# misc_A.net
KiCad netlist of a schematic drawn in Altium Designer
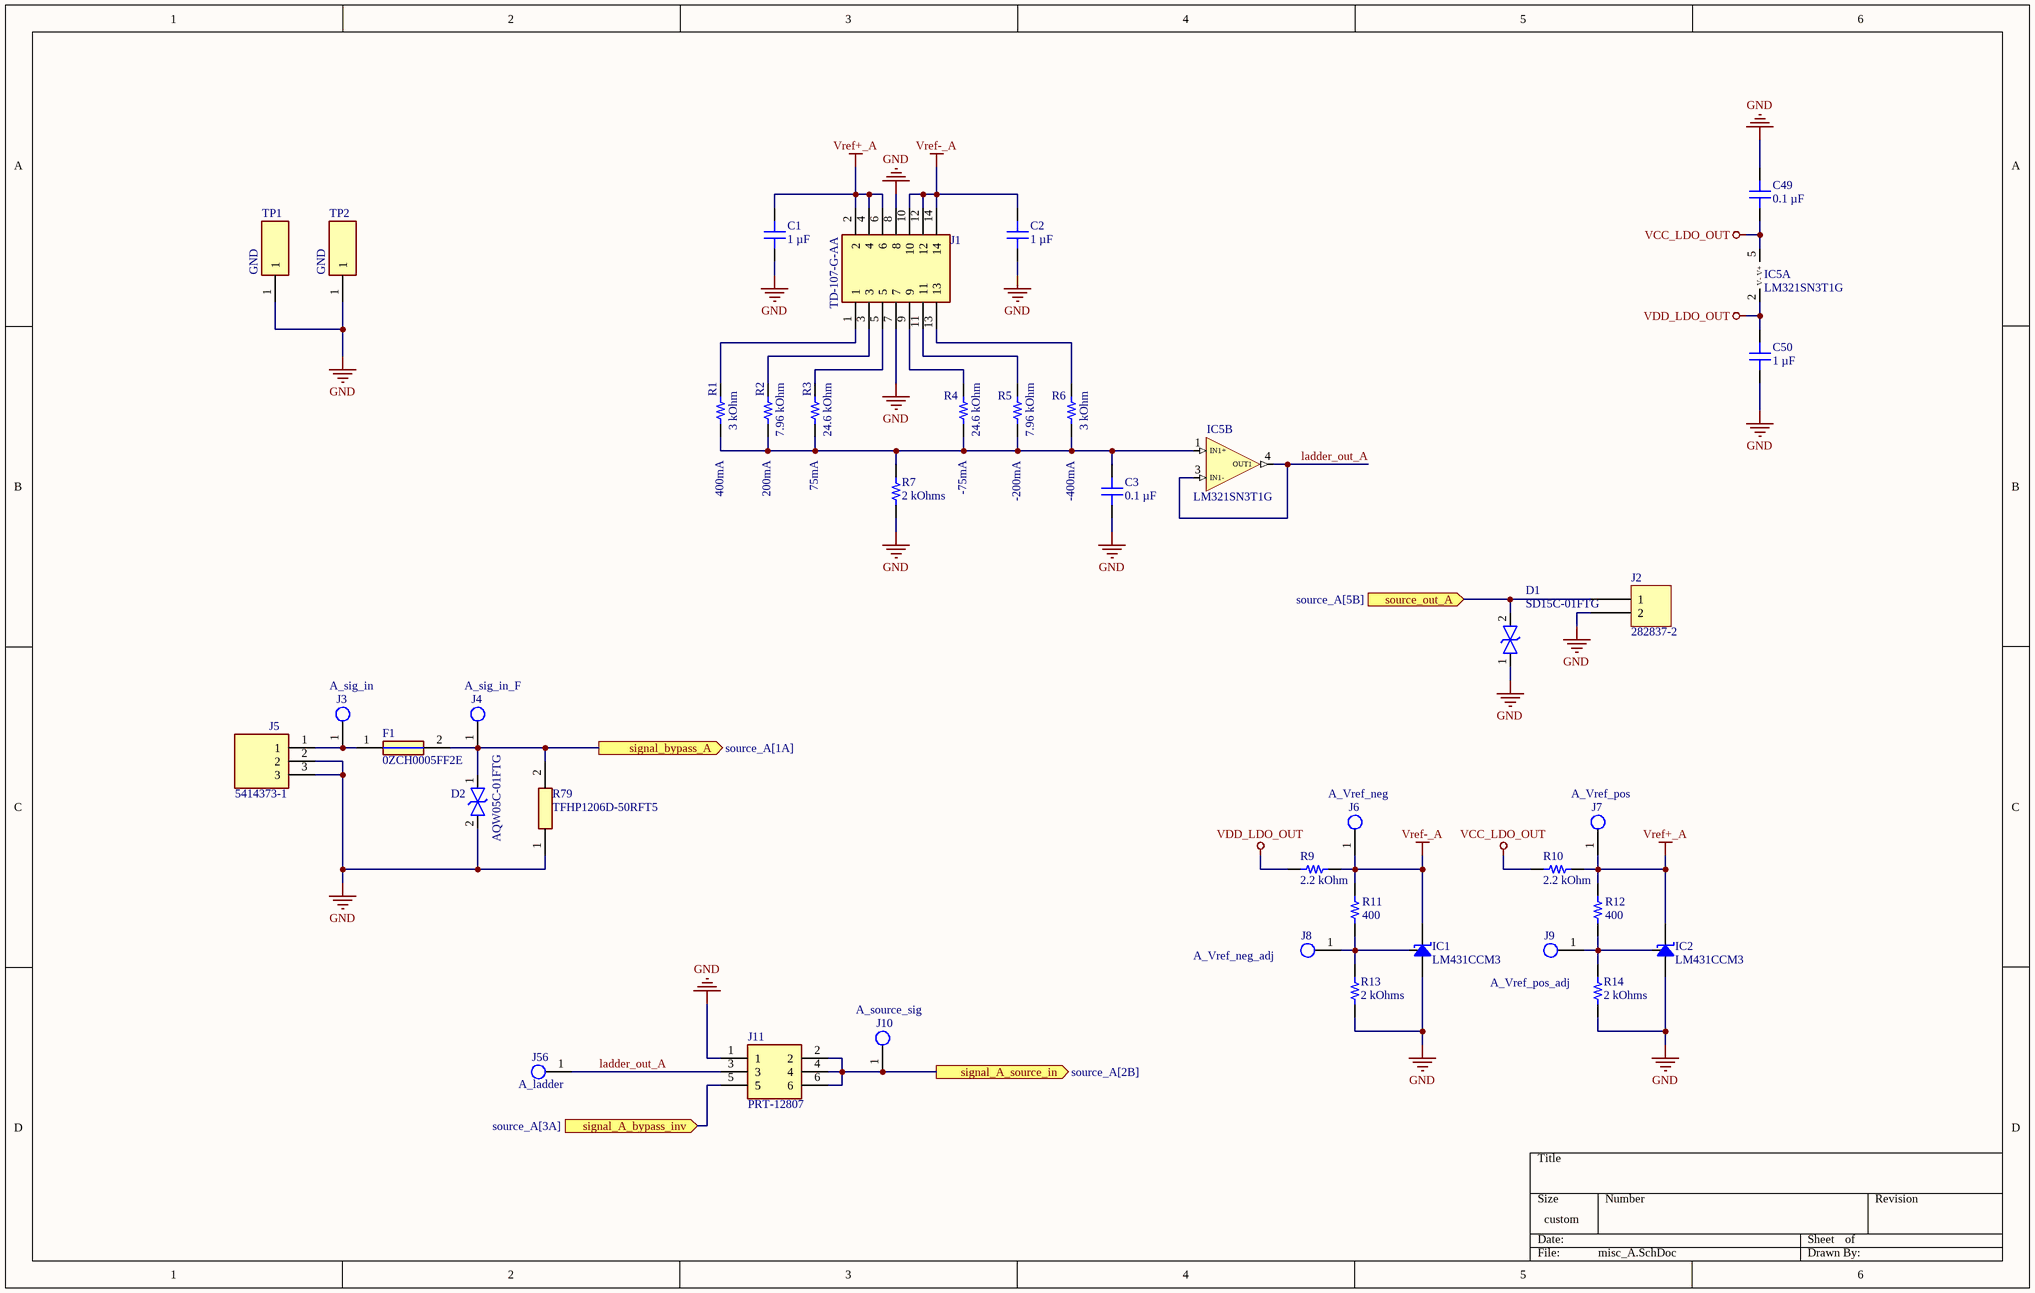
[diagram p0: misc_A.SchDoc]

(export (version "E")
  (design (tool "Eeschema 10.0.6"))
  (components
    (comp (ref "C1")
      (value "1 µF")
      (footprint "CAP 1206_3216 - 0.8MM")
      (description "CAP CER 1UF 50V X7R 1206")
      (fields
        (field (name "PART NUMBER") "885012208093")
        (field (name "CAPACITANCE") "1 µF")
        (field (name "MANUFACTURER") "Würth Elektronik")
      )
      (libsource (lib "Celestial Altium Library - altium_library") (part "Capacitor"))
    )
    (comp (ref "C2")
      (value "1 µF")
      (footprint "CAP 1206_3216 - 0.8MM")
      (description "CAP CER 1UF 50V X7R 1206")
      (fields
        (field (name "PART NUMBER") "885012208093")
        (field (name "CAPACITANCE") "1 µF")
        (field (name "MANUFACTURER") "Würth Elektronik")
      )
      (libsource (lib "Celestial Altium Library - altium_library") (part "Capacitor"))
    )
    (comp (ref "C3")
      (value "0.1 µF")
      (footprint "CAP 1206_3216 - 0.8MM")
      (description "CAP CER 0.1UF 50V X7R 1206")
      (fields
        (field (name "PART NUMBER") "885012208087")
        (field (name "CAPACITANCE") "0.1 µF")
        (field (name "MANUFACTURER") "Würth Elektronik")
      )
      (libsource (lib "Celestial Altium Library - altium_library") (part "Capacitor"))
    )
    (comp (ref "C49")
      (value "0.1 µF")
      (footprint "CAP 1206_3216 - 0.8MM")
      (description "CAP CER 0.1UF 50V X7R 1206")
      (fields
        (field (name "PART NUMBER") "885012208087")
        (field (name "CAPACITANCE") "0.1 µF")
        (field (name "MANUFACTURER") "Würth Elektronik")
      )
      (libsource (lib "Celestial Altium Library - altium_library") (part "Capacitor"))
    )
    (comp (ref "C50")
      (value "1 µF")
      (footprint "CAP 1206_3216 - 0.8MM")
      (description "CAP CER 1UF 50V X7R 1206")
      (fields
        (field (name "PART NUMBER") "885012208093")
        (field (name "CAPACITANCE") "1 µF")
        (field (name "MANUFACTURER") "Würth Elektronik")
      )
      (libsource (lib "Celestial Altium Library - altium_library") (part "Capacitor"))
    )
    (comp (ref "D1")
      (value "SD15C-01FTG")
      (footprint "za_koncar:SD15C01FTG")
      (description "TVS Diode (Bi-directional)")
      (fields (field (name "MOUSER PART NUMBER") "576-SD15C-01FTG"))
      (libsource (lib "za_koncar") (part "SD15C-01FTG"))
    )
    (comp (ref "D2")
      (value "AQW05C-01FTG")
      (footprint "SOD2613X100N")
      (description "TVS Diode (Bi-directional)")
      (fields (field (name "MOUSER PART NUMBER") "576-AQW05C-01FTG"))
      (libsource (lib "za_koncar") (part "AQW05C-01FTG"))
    )
    (comp (ref "F1")
      (value "0ZCH0005FF2E")
      (footprint "FUSC3226X115N")
      (description "Fuse")
      (fields (field (name "MOUSER PART NUMBER") "530-0ZCH0005FF2E"))
      (libsource (lib "za_koncar") (part "0ZCH0005FF2E"))
    )
    (comp (ref "IC1")
      (value "LM431CCM3")
      (footprint "SOT96P240X110-3N")
      (description "Integrated Circuit")
      (fields
        (field (name "MANUFACTURER_PART_NUMBER") "LM431CCM3/NOPB")
        (field (name "MOUSER PART NUMBER") "926-LM431CCM3/NOPB")
      )
      (libsource (lib "za_koncar") (part "LM431CCM3/NOPB"))
    )
    (comp (ref "IC2")
      (value "LM431CCM3")
      (footprint "SOT96P240X110-3N")
      (description "Integrated Circuit")
      (fields
        (field (name "MANUFACTURER_PART_NUMBER") "LM431CCM3/NOPB")
        (field (name "MOUSER PART NUMBER") "926-LM431CCM3/NOPB")
      )
      (libsource (lib "za_koncar") (part "LM431CCM3/NOPB"))
    )
    (comp (ref "IC5")
      (value "LM321SN3T1G")
      (footprint "za_koncar:SOT95P275X110-5N")
      (description "Integrated Circuit")
      (fields (field (name "MOUSER PART NUMBER") "863-LM321SN3T1G"))
      (libsource (lib "za_koncar") (part "LM321SN3T1G"))
    )
    (comp (ref "J1")
      (value "TD-107-G-AA")
      (footprint "HDRV14W46P254_2X7_1778X508X818P")
      (description "Connector")
      (fields (field (name "MOUSER PART NUMBER") "200-TD107GAA"))
      (libsource (lib "za_koncar") (part "TD-107-G-AA"))
    )
    (comp (ref "J2")
      (value "282837-2")
      (footprint "TE 282837-2")
      (description "TERM BLK 2P SIDE ENT 5.08MM PCB")
      (fields (field (name "MANUFACTURER") "TE Connectivity AMP Connectors") (field (name "VOLTAGE") "300 V"))
      (libsource (lib "Celestial Altium Library - altium_library") (part "2 Pin"))
    )
    (comp (ref "J3")
      (value "A_sig_in")
      (footprint "FP-5001-MFG")
      (description "PC TEST POINT MINIATURE BLACK")
      (libsource (lib "za_koncar") (part "5001"))
    )
    (comp (ref "J4")
      (value "A_sig_in_F")
      (footprint "FP-5001-MFG")
      (description "PC TEST POINT MINIATURE BLACK")
      (libsource (lib "za_koncar") (part "5001"))
    )
    (comp (ref "J5")
      (value "5414373-1")
      (footprint "za_koncar:54143731")
      (description "Connector")
      (fields (field (name "MOUSER PART NUMBER") "571-5414373-1"))
      (libsource (lib "za_koncar") (part "5414373-1"))
    )
    (comp (ref "J6")
      (value "A_Vref_neg")
      (footprint "FP-5001-MFG")
      (description "PC TEST POINT MINIATURE BLACK")
      (libsource (lib "za_koncar") (part "5001"))
    )
    (comp (ref "J7")
      (value "A_Vref_pos")
      (footprint "FP-5001-MFG")
      (description "PC TEST POINT MINIATURE BLACK")
      (libsource (lib "za_koncar") (part "5001"))
    )
    (comp (ref "J8")
      (value "A_Vref_neg_adj")
      (footprint "FP-5001-MFG")
      (description "PC TEST POINT MINIATURE BLACK")
      (libsource (lib "za_koncar") (part "5001"))
    )
    (comp (ref "J9")
      (value "A_Vref_pos_adj")
      (footprint "FP-5001-MFG")
      (description "PC TEST POINT MINIATURE BLACK")
      (libsource (lib "za_koncar") (part "5001"))
    )
    (comp (ref "J10")
      (value "A_source_sig")
      (footprint "FP-5001-MFG")
      (description "PC TEST POINT MINIATURE BLACK")
      (libsource (lib "za_koncar") (part "5001"))
    )
    (comp (ref "J11")
      (value "PRT-12807")
      (footprint "HDRV6W82P254_2X3_762X500X884P")
      (description "Connector")
      (fields (field (name "MOUSER PART NUMBER") "474-PRT-12807"))
      (libsource (lib "za_koncar") (part "PRT-12807"))
    )
    (comp (ref "J56")
      (value "A_ladder")
      (footprint "FP-5001-MFG")
      (description "PC TEST POINT MINIATURE BLACK")
      (libsource (lib "za_koncar") (part "5001"))
    )
    (comp (ref "R1")
      (value "3 kOhm")
      (footprint "za_koncar:ERA3AEB101V")
      (description "Resistor")
      (fields
        (field (name "MANUFACTURER_PART_NUMBER") "ERA-3AEB302V")
        (field (name "MOUSER PART NUMBER") "667-ERA-3AEB302V")
      )
      (libsource (lib "za_koncar") (part "ERA-3AEB302V"))
    )
    (comp (ref "R2")
      (value "7.96 kOhm")
      (footprint "za_koncar:ERA3AEB101V")
      (description "Resistor")
      (fields
        (field (name "MANUFACTURER_PART_NUMBER") "ERA-3AEB302V")
        (field (name "MOUSER PART NUMBER") "667-ERA-3AEB302V")
      )
      (libsource (lib "za_koncar") (part "TNPW06037K96BEEA"))
    )
    (comp (ref "R3")
      (value "24.6 kOhm")
      (footprint "za_koncar:ERA3AEB101V")
      (description "Resistor")
      (fields
        (field (name "MANUFACTURER_PART_NUMBER") "ERA-3AEB302V")
        (field (name "MOUSER PART NUMBER") "667-ERA-3AEB302V")
      )
      (libsource (lib "za_koncar") (part "RT0603BRD0724K6L"))
    )
    (comp (ref "R4")
      (value "24.6 kOhm")
      (footprint "za_koncar:ERA3AEB101V")
      (description "Resistor")
      (fields
        (field (name "MANUFACTURER_PART_NUMBER") "ERA-3AEB302V")
        (field (name "MOUSER PART NUMBER") "667-ERA-3AEB302V")
      )
      (libsource (lib "za_koncar") (part "RT0603BRD0724K6L"))
    )
    (comp (ref "R5")
      (value "7.96 kOhm")
      (footprint "za_koncar:ERA3AEB101V")
      (description "Resistor")
      (fields
        (field (name "MANUFACTURER_PART_NUMBER") "ERA-3AEB302V")
        (field (name "MOUSER PART NUMBER") "667-ERA-3AEB302V")
      )
      (libsource (lib "za_koncar") (part "TNPW06037K96BEEA"))
    )
    (comp (ref "R6")
      (value "3 kOhm")
      (footprint "za_koncar:ERA3AEB101V")
      (description "Resistor")
      (fields
        (field (name "MANUFACTURER_PART_NUMBER") "ERA-3AEB302V")
        (field (name "MOUSER PART NUMBER") "667-ERA-3AEB302V")
      )
      (libsource (lib "za_koncar") (part "ERA-3AEB302V"))
    )
    (comp (ref "R7")
      (value "2 kOhms")
      (footprint "RES 1206_3216")
      (description "RES SMD 2K OHM 0.1% 1/4W 1206")
      (fields
        (field (name "PART NUMBER") "ERA-8AEB202V")
        (field (name "MANUFACTURER") "Panasonic Electronic Components")
      )
      (libsource (lib "Celestial Altium Library - altium_library") (part "Resistor"))
    )
    (comp (ref "R9")
      (value "2.2 kOhm")
      (footprint "za_koncar:RESC3116X65N")
      (description "Resistor")
      (fields
        (field (name "MANUFACTURER_PART_NUMBER") "RT1206FRE072K2L")
        (field (name "MOUSER PART NUMBER") "603-RT1206FRE072K2L")
      )
      (libsource (lib "za_koncar") (part "RT1206FRE072K2L"))
    )
    (comp (ref "R10")
      (value "2.2 kOhm")
      (footprint "za_koncar:RESC3116X65N")
      (description "Resistor")
      (fields
        (field (name "MANUFACTURER_PART_NUMBER") "RT1206FRE072K2L")
        (field (name "MOUSER PART NUMBER") "603-RT1206FRE072K2L")
      )
      (libsource (lib "za_koncar") (part "RT1206FRE072K2L"))
    )
    (comp (ref "R11")
      (value "400")
      (footprint "RESC3116X65N")
      (description "Resistor")
      (fields
        (field (name "MANUFACTURER_PART_NUMBER") "RT1206BRD07400RL")
        (field (name "MOUSER PART NUMBER") "603-RT1206BRD07400RL")
      )
      (libsource (lib "za_koncar") (part "RT1206BRD07400RL"))
    )
    (comp (ref "R12")
      (value "400")
      (footprint "RESC3116X65N")
      (description "Resistor")
      (fields
        (field (name "MANUFACTURER_PART_NUMBER") "RT1206BRD07400RL")
        (field (name "MOUSER PART NUMBER") "603-RT1206BRD07400RL")
      )
      (libsource (lib "za_koncar") (part "RT1206BRD07400RL"))
    )
    (comp (ref "R13")
      (value "2 kOhms")
      (footprint "RES 1206_3216")
      (description "RES SMD 2K OHM 0.1% 1/4W 1206")
      (fields
        (field (name "PART NUMBER") "ERA-8AEB202V")
        (field (name "MANUFACTURER") "Panasonic Electronic Components")
      )
      (libsource (lib "Celestial Altium Library - altium_library") (part "Resistor"))
    )
    (comp (ref "R14")
      (value "2 kOhms")
      (footprint "RES 1206_3216")
      (description "RES SMD 2K OHM 0.1% 1/4W 1206")
      (fields
        (field (name "PART NUMBER") "ERA-8AEB202V")
        (field (name "MANUFACTURER") "Panasonic Electronic Components")
      )
      (libsource (lib "Celestial Altium Library - altium_library") (part "Resistor"))
    )
    (comp (ref "R79")
      (value "TFHP1206D-50RFT5")
      (footprint "RESC3016X58N")
      (description "Resistor")
      (fields (field (name "MOUSER PART NUMBER") "756-TFHP1206B-50RFT5"))
      (libsource (lib "za_koncar") (part "TFHP1206D-50RFT5"))
    )
    (comp (ref "TP1")
      (value "GND")
      (footprint "za_koncar:S175146R")
      (description "Test Point")
      (fields
        (field (name "MANUFACTURER_PART_NUMBER") "S1751-46R")
        (field (name "MOUSER PART NUMBER") "855-S1751-46R")
      )
      (libsource (lib "za_koncar") (part "S1751-46R"))
    )
    (comp (ref "TP2")
      (value "GND")
      (footprint "za_koncar:S175146R")
      (description "Test Point")
      (fields
        (field (name "MANUFACTURER_PART_NUMBER") "S1751-46R")
        (field (name "MOUSER PART NUMBER") "855-S1751-46R")
      )
      (libsource (lib "za_koncar") (part "S1751-46R"))
    )
  )
  (nets
    (net (code "1") (name "/ladder_out_A") (class "Default")
      (node (ref "IC5") (pin "3") (pinfunction "IN1-_3") (pintype "input"))
      (node (ref "IC5") (pin "4") (pinfunction "OUT1_4") (pintype "output"))
      (node (ref "J11") (pin "3") (pinfunction "3_3") (pintype "passive"))
      (node (ref "J56") (pin "1") (pinfunction "1_1") (pintype "passive"))
    )
    (net (code "2") (name "/signal_A_bypass_inv") (class "Default")
      (node (ref "J11") (pin "5") (pinfunction "5_5") (pintype "passive"))
    )
    (net (code "3") (name "/signal_A_source_in") (class "Default")
      (node (ref "J10") (pin "1") (pinfunction "1_1") (pintype "passive"))
      (node (ref "J11") (pin "2") (pinfunction "2_2") (pintype "passive"))
      (node (ref "J11") (pin "4") (pinfunction "4_4") (pintype "passive"))
      (node (ref "J11") (pin "6") (pinfunction "6_6") (pintype "passive"))
    )
    (net (code "4") (name "/signal_bypass_A") (class "Default")
      (node (ref "D2") (pin "1") (pinfunction "1_1") (pintype "passive"))
      (node (ref "F1") (pin "2") (pinfunction "2_2") (pintype "passive"))
      (node (ref "J4") (pin "1") (pinfunction "1_1") (pintype "passive"))
      (node (ref "R79") (pin "2") (pinfunction "2_2") (pintype "passive"))
    )
    (net (code "5") (name "/source_out_A") (class "Default")
      (node (ref "D1") (pin "2") (pinfunction "2_2") (pintype "passive"))
      (node (ref "J2") (pin "1") (pinfunction "1_1") (pintype "passive"))
    )
    (net (code "6") (name "GND") (class "Default")
      (node (ref "C1") (pin "2") (pinfunction "2_2") (pintype "passive"))
      (node (ref "C2") (pin "1") (pinfunction "1_1") (pintype "passive"))
      (node (ref "C3") (pin "2") (pinfunction "2_2") (pintype "passive"))
      (node (ref "C49") (pin "1") (pinfunction "1_1") (pintype "passive"))
      (node (ref "C50") (pin "2") (pinfunction "2_2") (pintype "passive"))
      (node (ref "D1") (pin "1") (pinfunction "1_1") (pintype "passive"))
      (node (ref "D2") (pin "2") (pinfunction "2_2") (pintype "passive"))
      (node (ref "IC1") (pin "2") (pinfunction "Anode_2") (pintype "passive"))
      (node (ref "IC2") (pin "2") (pinfunction "Anode_2") (pintype "passive"))
      (node (ref "J1") (pin "7") (pinfunction "7_7") (pintype "passive"))
      (node (ref "J1") (pin "8") (pinfunction "8_8") (pintype "passive"))
      (node (ref "J11") (pin "1") (pinfunction "1_1") (pintype "passive"))
      (node (ref "J2") (pin "2") (pinfunction "2_2") (pintype "passive"))
      (node (ref "J5") (pin "2") (pinfunction "2_2") (pintype "passive"))
      (node (ref "J5") (pin "3") (pinfunction "3_3") (pintype "passive"))
      (node (ref "R13") (pin "1") (pinfunction "1_1") (pintype "passive"))
      (node (ref "R14") (pin "1") (pinfunction "1_1") (pintype "passive"))
      (node (ref "R7") (pin "1") (pinfunction "1_1") (pintype "passive"))
      (node (ref "R79") (pin "1") (pinfunction "1_1") (pintype "passive"))
      (node (ref "TP1") (pin "1") (pinfunction "1_1") (pintype "passive"))
      (node (ref "TP2") (pin "1") (pinfunction "1_1") (pintype "passive"))
    )
    (net (code "7") (name "Net-(F1-Pad1)") (class "Default")
      (node (ref "F1") (pin "1") (pinfunction "1_1") (pintype "passive"))
      (node (ref "J3") (pin "1") (pinfunction "1_1") (pintype "passive"))
      (node (ref "J5") (pin "1") (pinfunction "1_1") (pintype "passive"))
    )
    (net (code "8") (name "Net-(IC1-Ref)") (class "Default")
      (node (ref "IC1") (pin "3") (pinfunction "Ref_3") (pintype "passive"))
      (node (ref "J8") (pin "1") (pinfunction "1_1") (pintype "passive"))
      (node (ref "R11") (pin "1") (pinfunction "1_1") (pintype "passive"))
      (node (ref "R13") (pin "2") (pinfunction "2_2") (pintype "passive"))
    )
    (net (code "9") (name "Net-(IC2-Ref)") (class "Default")
      (node (ref "IC2") (pin "3") (pinfunction "Ref_3") (pintype "passive"))
      (node (ref "J9") (pin "1") (pinfunction "1_1") (pintype "passive"))
      (node (ref "R12") (pin "1") (pinfunction "1_1") (pintype "passive"))
      (node (ref "R14") (pin "2") (pinfunction "2_2") (pintype "passive"))
    )
    (net (code "10") (name "Net-(IC5B-IN1+)") (class "Default")
      (node (ref "C3") (pin "1") (pinfunction "1_1") (pintype "passive"))
      (node (ref "IC5") (pin "1") (pinfunction "IN1+_1") (pintype "input"))
      (node (ref "R1") (pin "1") (pinfunction "1_1") (pintype "passive"))
      (node (ref "R2") (pin "1") (pinfunction "1_1") (pintype "passive"))
      (node (ref "R3") (pin "1") (pinfunction "1_1") (pintype "passive"))
      (node (ref "R4") (pin "1") (pinfunction "1_1") (pintype "passive"))
      (node (ref "R5") (pin "1") (pinfunction "1_1") (pintype "passive"))
      (node (ref "R6") (pin "1") (pinfunction "1_1") (pintype "passive"))
      (node (ref "R7") (pin "2") (pinfunction "2_2") (pintype "passive"))
    )
    (net (code "11") (name "Net-(J1-Pad1)") (class "Default")
      (node (ref "J1") (pin "1") (pinfunction "1_1") (pintype "passive"))
      (node (ref "R1") (pin "2") (pinfunction "2_2") (pintype "passive"))
    )
    (net (code "12") (name "Net-(J1-Pad3)") (class "Default")
      (node (ref "J1") (pin "3") (pinfunction "3_3") (pintype "passive"))
      (node (ref "R2") (pin "2") (pinfunction "2_2") (pintype "passive"))
    )
    (net (code "13") (name "Net-(J1-Pad5)") (class "Default")
      (node (ref "J1") (pin "5") (pinfunction "5_5") (pintype "passive"))
      (node (ref "R3") (pin "2") (pinfunction "2_2") (pintype "passive"))
    )
    (net (code "14") (name "Net-(J1-Pad9)") (class "Default")
      (node (ref "J1") (pin "9") (pinfunction "9_9") (pintype "passive"))
      (node (ref "R4") (pin "2") (pinfunction "2_2") (pintype "passive"))
    )
    (net (code "15") (name "Net-(J1-Pad11)") (class "Default")
      (node (ref "J1") (pin "11") (pinfunction "11_11") (pintype "passive"))
      (node (ref "R5") (pin "2") (pinfunction "2_2") (pintype "passive"))
    )
    (net (code "16") (name "Net-(J1-Pad13)") (class "Default")
      (node (ref "J1") (pin "13") (pinfunction "13_13") (pintype "passive"))
      (node (ref "R6") (pin "2") (pinfunction "2_2") (pintype "passive"))
    )
    (net (code "17") (name "VCC_LDO_OUT") (class "Default")
      (node (ref "C49") (pin "2") (pinfunction "2_2") (pintype "passive"))
      (node (ref "IC5") (pin "5") (pinfunction "V+_5") (pintype "power_in"))
      (node (ref "R10") (pin "2") (pinfunction "2_2") (pintype "passive"))
    )
    (net (code "18") (name "VDD_LDO_OUT") (class "Default")
      (node (ref "C50") (pin "1") (pinfunction "1_1") (pintype "passive"))
      (node (ref "IC5") (pin "2") (pinfunction "V-_2") (pintype "power_in"))
      (node (ref "R9") (pin "2") (pinfunction "2_2") (pintype "passive"))
    )
    (net (code "19") (name "Vref+_A") (class "Default")
      (node (ref "C1") (pin "1") (pinfunction "1_1") (pintype "passive"))
      (node (ref "IC2") (pin "1") (pinfunction "Cathode_1") (pintype "passive"))
      (node (ref "J1") (pin "2") (pinfunction "2_2") (pintype "passive"))
      (node (ref "J1") (pin "4") (pinfunction "4_4") (pintype "passive"))
      (node (ref "J1") (pin "6") (pinfunction "6_6") (pintype "passive"))
      (node (ref "J7") (pin "1") (pinfunction "1_1") (pintype "passive"))
      (node (ref "R10") (pin "1") (pinfunction "1_1") (pintype "passive"))
      (node (ref "R12") (pin "2") (pinfunction "2_2") (pintype "passive"))
    )
    (net (code "20") (name "Vref-_A") (class "Default")
      (node (ref "C2") (pin "2") (pinfunction "2_2") (pintype "passive"))
      (node (ref "IC1") (pin "1") (pinfunction "Cathode_1") (pintype "passive"))
      (node (ref "J1") (pin "10") (pinfunction "10_10") (pintype "passive"))
      (node (ref "J1") (pin "12") (pinfunction "12_12") (pintype "passive"))
      (node (ref "J1") (pin "14") (pinfunction "14_14") (pintype "passive"))
      (node (ref "J6") (pin "1") (pinfunction "1_1") (pintype "passive"))
      (node (ref "R11") (pin "2") (pinfunction "2_2") (pintype "passive"))
      (node (ref "R9") (pin "1") (pinfunction "1_1") (pintype "passive"))
    )
  )
)
